# SparkFun_Infrared_Proximity_Breakout-VCN.net
KiCad netlist of a schematic drawn in EAGLE
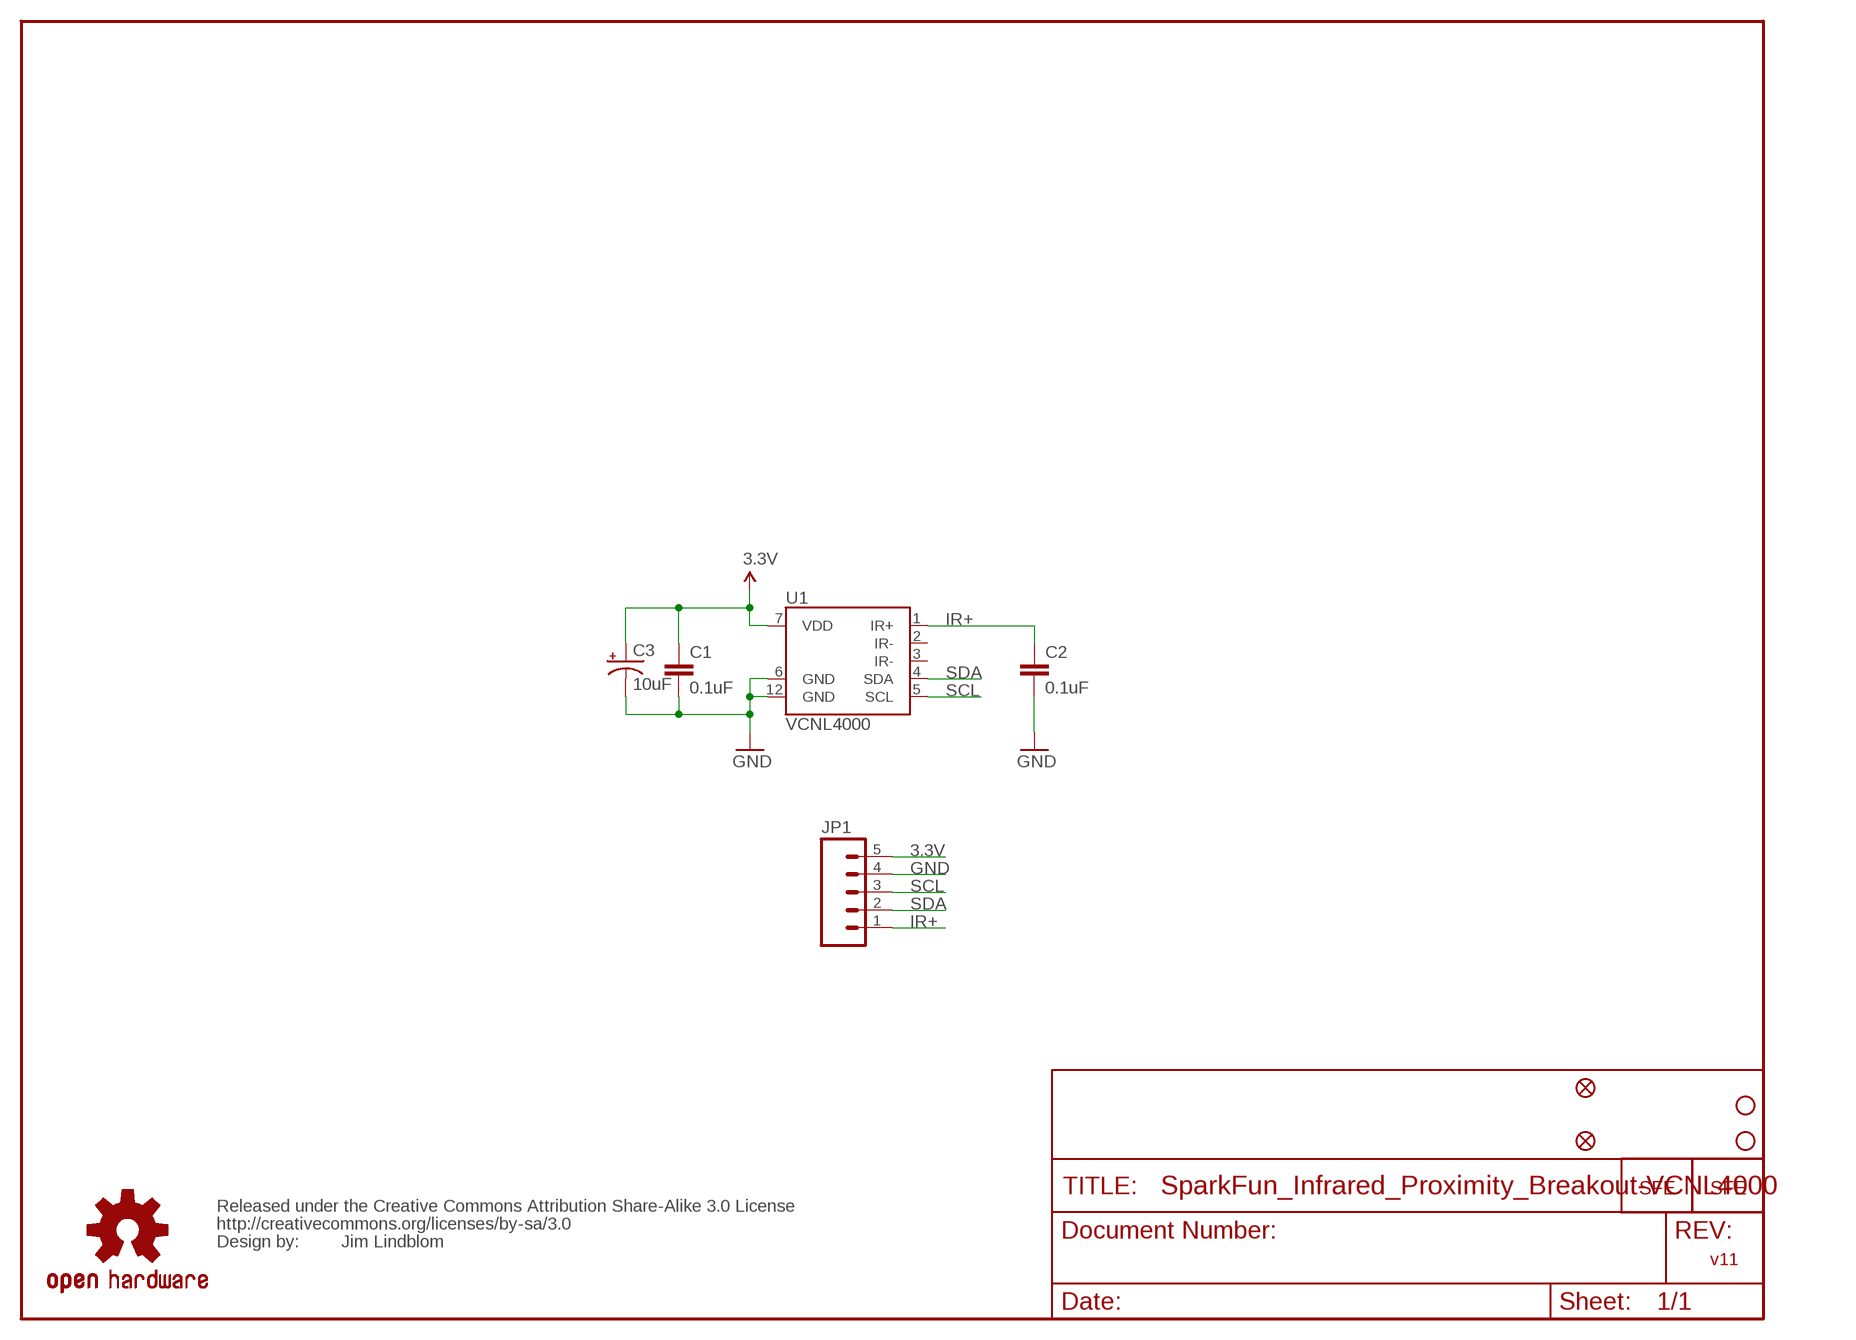
[diagram p0: schematic, sheet 1]

(export (version "E")
  (design (tool "Eeschema 10.0.6"))
  (components
    (comp (ref "C1")
      (value "0.1uF")
      (footprint "eagle-import:0402-CAP")
      (libsource (lib "eagle-import") (part "CAP0402-CAP"))
    )
    (comp (ref "C2")
      (value "0.1uF")
      (footprint "eagle-import:0402-CAP")
      (libsource (lib "eagle-import") (part "CAP0402-CAP"))
    )
    (comp (ref "C3")
      (value "10uF")
      (footprint "eagle-import:EIA3216")
      (libsource (lib "eagle-import") (part "CAP_POL1206"))
    )
    (comp (ref "JP1")
      (value "M05PTH")
      (footprint "eagle-import:1X05")
      (libsource (lib "eagle-import") (part "M05PTH"))
    )
    (comp (ref "JP2")
      (value "LOGO-SFENW2")
      (footprint "eagle-import:SFE-NEW-WEB")
      (libsource (lib "eagle-import") (part "LOGO-SFENW2"))
    )
    (comp (ref "JP3")
      (value "STAND-OFF")
      (footprint "eagle-import:STAND-OFF")
      (libsource (lib "eagle-import") (part "STAND-OFF"))
    )
    (comp (ref "JP4")
      (value "STAND-OFF")
      (footprint "eagle-import:STAND-OFF")
      (libsource (lib "eagle-import") (part "STAND-OFF"))
    )
    (comp (ref "JP5")
      (value "LOGO-SFESK")
      (footprint "eagle-import:SFE-LOGO-FLAME")
      (libsource (lib "eagle-import") (part "LOGO-SFESK"))
    )
    (comp (ref "JP6")
      (value "FIDUCIALUFIDUCIAL")
      (footprint "eagle-import:MICRO-FIDUCIAL")
      (libsource (lib "eagle-import") (part "FIDUCIALUFIDUCIAL"))
    )
    (comp (ref "JP7")
      (value "FIDUCIALUFIDUCIAL")
      (footprint "eagle-import:MICRO-FIDUCIAL")
      (libsource (lib "eagle-import") (part "FIDUCIALUFIDUCIAL"))
    )
    (comp (ref "U$1")
      (value "OSHW-LOGOS")
      (footprint "eagle-import:OSHW-LOGO-S")
      (libsource (lib "eagle-import") (part "OSHW-LOGOS"))
    )
    (comp (ref "U$2")
      (value "CREATIVE_COMMONS")
      (footprint "eagle-import:CREATIVE_COMMONS")
      (libsource (lib "eagle-import") (part "CREATIVE_COMMONS"))
    )
    (comp (ref "U1")
      (value "VCNL4000")
      (footprint "eagle-import:VCNL4000")
      (libsource (lib "eagle-import") (part "VCNL4000"))
    )
  )
  (nets
    (net (code "1") (name "/IR+") (class "Default")
      (node (ref "C2") (pin "1") (pinfunction "1_1") (pintype "passive"))
      (node (ref "JP1") (pin "1") (pinfunction "1_1") (pintype "passive"))
      (node (ref "U1") (pin "1") (pinfunction "IR+_1") (pintype "bidirectional"))
    )
    (net (code "2") (name "/SCL") (class "Default")
      (node (ref "JP1") (pin "3") (pinfunction "3_3") (pintype "passive"))
      (node (ref "U1") (pin "5") (pinfunction "SCL_5") (pintype "bidirectional"))
    )
    (net (code "3") (name "/SDA") (class "Default")
      (node (ref "JP1") (pin "2") (pinfunction "2_2") (pintype "passive"))
      (node (ref "U1") (pin "4") (pinfunction "SDA_4") (pintype "bidirectional"))
    )
    (net (code "4") (name "3.3V") (class "Default")
      (node (ref "C1") (pin "1") (pinfunction "1_1") (pintype "passive"))
      (node (ref "C3") (pin "A") (pinfunction "+_A") (pintype "passive"))
      (node (ref "JP1") (pin "5") (pinfunction "5_5") (pintype "passive"))
      (node (ref "U1") (pin "7") (pinfunction "VDD_7") (pintype "bidirectional"))
    )
    (net (code "5") (name "GND") (class "Default")
      (node (ref "C1") (pin "2") (pinfunction "2_2") (pintype "passive"))
      (node (ref "C2") (pin "2") (pinfunction "2_2") (pintype "passive"))
      (node (ref "C3") (pin "C") (pinfunction "-_C") (pintype "passive"))
      (node (ref "JP1") (pin "4") (pinfunction "4_4") (pintype "passive"))
      (node (ref "U1") (pin "12") (pinfunction "GND_12") (pintype "bidirectional"))
      (node (ref "U1") (pin "6") (pinfunction "GND_6") (pintype "bidirectional"))
    )
    (net (code "6") (name "unconnected-(U1-IR--Pad2)") (class "Default")
      (node (ref "U1") (pin "2") (pinfunction "IR-_2") (pintype "bidirectional"))
    )
    (net (code "7") (name "unconnected-(U1-IR--Pad3)") (class "Default")
      (node (ref "U1") (pin "3") (pinfunction "IR-_3") (pintype "bidirectional"))
    )
  )
)
